# LM399.net
KiCad netlist of a schematic drawn in Altium Designer
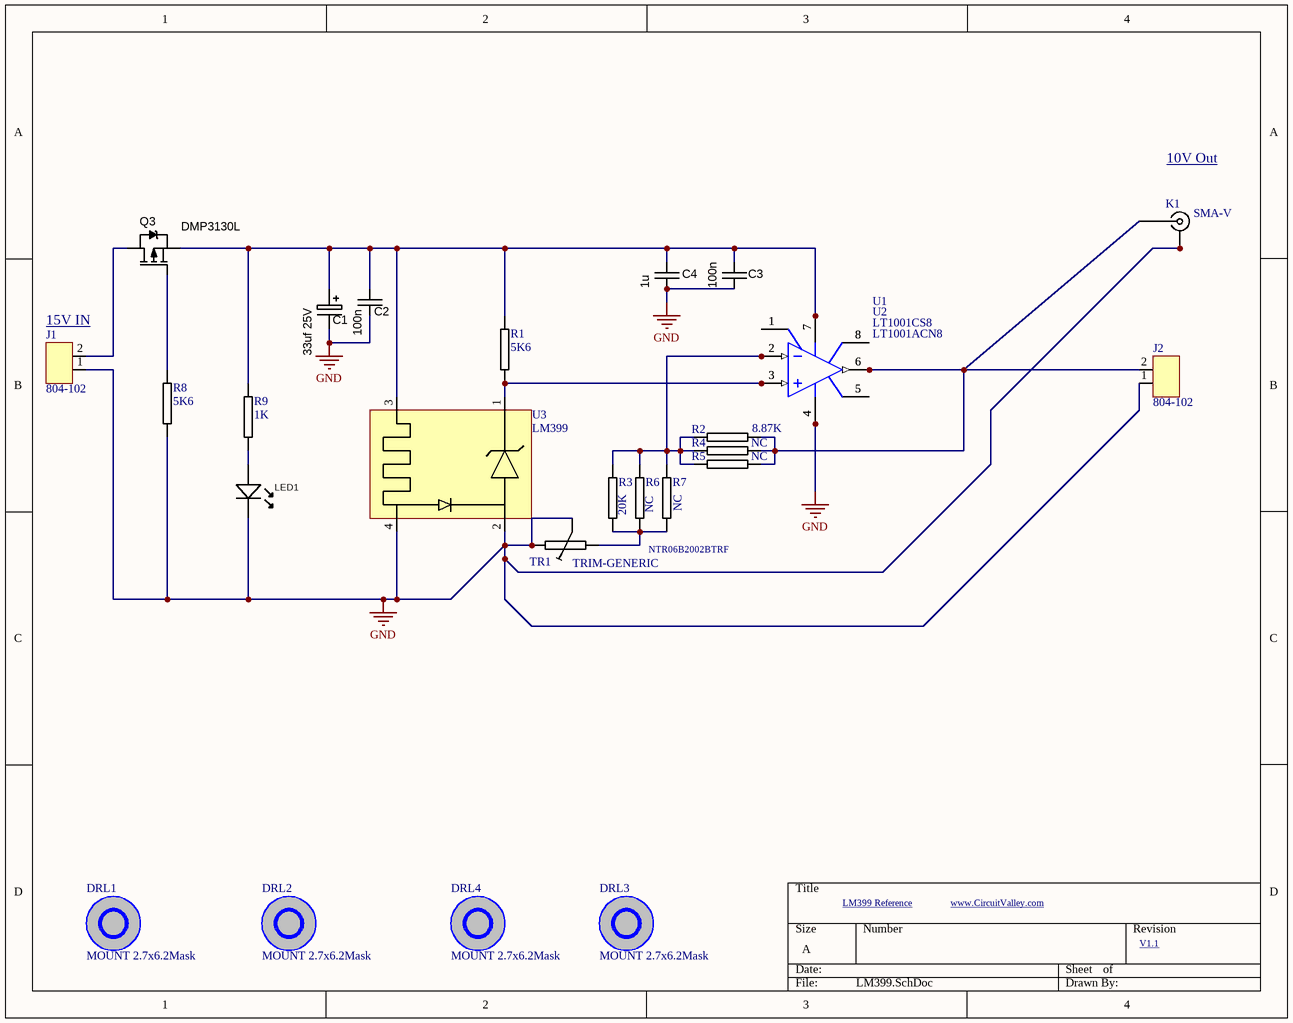
[diagram p0: LM399.SchDoc]

(export (version "E")
  (design (tool "Eeschema 10.0.6"))
  (components
    (comp (ref "C1")
      (value "33uf 25V")
      (footprint "CAPMP7343X310N")
      (description "Capacitor SMD Tant 330uF 20% 6V3 2917")
      (fields
        (field (name "TOLERANCE") "±20%")
        (field (name "MANUFACTURER PART NUMBER") "T520D337M006ATE015")
      )
      (libsource (lib "PBL - Capacitors") (part "CAPT_330u_2917_6V3"))
    )
    (comp (ref "C2")
      (value "100n")
      (footprint "CAPC1608N")
      (description "Capacitor SMD Cer 10pF 5% 50V NP0 0603")
      (fields (field (name "TOLERANCE") "±5%") (field (name "PART") "C0603X104K5RAC"))
      (libsource (lib "PBL - Capacitors") (part "CAPC_10p_0603_NP0_1%_50V"))
    )
    (comp (ref "C3")
      (value "100n")
      (footprint "CAPC1608N")
      (description "Capacitor SMD Cer 10pF 5% 50V NP0 0603")
      (fields (field (name "PART") "C0603X104K5RAC"))
      (libsource (lib "PBL - Capacitors") (part "CAPC_10p_0603_NP0_1%_50V"))
    )
    (comp (ref "C4")
      (value "1u")
      (footprint "CAPC1608N")
      (description "Capacitor SMD Cer 10pF 5% 50V NP0 0603")
      (fields (field (name "TOLERANCE") "±5%") (field (name "PART") "C0603X104K5RAC"))
      (libsource (lib "PBL - Capacitors") (part "CAPC_10p_0603_NP0_1%_50V"))
    )
    (comp (ref "DRL1")
      (value "MOUNT 2.7x6.2Mask")
      (footprint "NO_COPPER_NOMASK_2m75_6m2")
      (libsource (lib "mounting_hole") (part "DRILL_2.7x6.2Mask_NOCOPPER"))
    )
    (comp (ref "DRL2")
      (value "MOUNT 2.7x6.2Mask")
      (footprint "NO_COPPER_NOMASK_2m75_6m2")
      (libsource (lib "mounting_hole") (part "DRILL_2.7x6.2Mask_NOCOPPER"))
    )
    (comp (ref "DRL3")
      (value "MOUNT 2.7x6.2Mask")
      (footprint "NO_COPPER_NOMASK_2m75_6m2")
      (libsource (lib "mounting_hole") (part "DRILL_2.7x6.2Mask_NOCOPPER"))
    )
    (comp (ref "DRL4")
      (value "MOUNT 2.7x6.2Mask")
      (footprint "NO_COPPER_NOMASK_2m75_6m2")
      (libsource (lib "mounting_hole") (part "DRILL_2.7x6.2Mask_NOCOPPER"))
    )
    (comp (ref "J1") (value "804-102") (footprint "804-102") (libsource (lib "") (part "804-102_1")))
    (comp (ref "J2") (value "804-102") (footprint "804-102") (libsource (lib "cvlib") (part "804-102")))
    (comp (ref "K1")
      (value "SMA-V")
      (footprint "SMA-V")
      (description "SMA THREADED RF CONNECTOR VERTICAL")
      (libsource (lib "Generic") (part "SMA-V"))
    )
    (comp (ref "LED1")
      (value "~")
      (footprint "LED-0805-K")
      (description "LED, 0805 SMD, Green")
      (libsource (lib "PBL - Light Sources") (part "LED_SMD_Green_0805"))
    )
    (comp (ref "Q3")
      (value "DMP3130L")
      (footprint "SOT23-3")
      (description "MOSFET SMD P-CH 50V 130mA SOT23-3")
      (libsource (lib "PBL - Transistors") (part "MOSFET_BSS84"))
    )
    (comp (ref "R1")
      (value "5K6")
      (footprint "0603R-GENERIC")
      (description "GENERIC RESISTOR 0603")
      (fields (field (name "PART") "RMCF0603JT7K50"))
      (libsource (lib "Generic") (part "0603R-7K5"))
    )
    (comp (ref "R2")
      (value "8.87K")
      (footprint "0603R-TBD")
      (description "RESISTOR 0603 VALUE TO BE DETERMINED")
      (fields (field (name "PART") "RN73C1J8K87BTG"))
      (libsource (lib "Generic") (part "0603R-TBD"))
    )
    (comp (ref "R3")
      (value "20K")
      (footprint "0603R-GENERIC")
      (description "GENERIC RESISTOR 0603")
      (fields (field (name "PART") "ERA-3ARW203V"))
      (libsource (lib "Generic") (part "0603R-20K"))
    )
    (comp (ref "R4")
      (value "NC")
      (footprint "0603R-TBD")
      (description "RESISTOR 0603 VALUE TO BE DETERMINED")
      (fields (field (name "PART") "RN73C1J8K87BTG"))
      (libsource (lib "Generic") (part "0603R-TBD"))
    )
    (comp (ref "R5")
      (value "NC")
      (footprint "0603R-TBD")
      (description "RESISTOR 0603 VALUE TO BE DETERMINED")
      (fields (field (name "PART") "RN73C1J8K87BTG"))
      (libsource (lib "Generic") (part "0603R-TBD"))
    )
    (comp (ref "R6")
      (value "NC")
      (footprint "0603R-GENERIC")
      (description "GENERIC RESISTOR 0603")
      (fields (field (name "PART") "ERA-3ARW203V"))
      (libsource (lib "Generic") (part "0603R-20K"))
    )
    (comp (ref "R7")
      (value "NC")
      (footprint "0603R-GENERIC")
      (description "GENERIC RESISTOR 0603")
      (fields (field (name "PART") "ERA-3ARW203V"))
      (libsource (lib "Generic") (part "0603R-20K"))
    )
    (comp (ref "R8")
      (value "5K6")
      (footprint "0603R-GENERIC")
      (description "GENERIC RESISTOR 0603")
      (fields (field (name "PART") "RMCF0603JT7K50"))
      (libsource (lib "Generic") (part "0603R-7K5"))
    )
    (comp (ref "R9")
      (value "1K")
      (footprint "0603R-120K")
      (description "GENERIC RESISTOR 0603")
      (fields
        (field (name "MANUFACTURER") "Stackpole Electronics Inc")
        (field (name "MANUFACTURER PART NUMBER") "RMCF 1/16 120K 1% R")
      )
      (libsource (lib "Generic") (part "0603R-120K"))
    )
    (comp (ref "TR1")
      (value "TRIM-GENERIC")
      (footprint "TRIMMER-MT")
      (description "TRIMMABLE RESISTOR")
      (libsource (lib "Generic") (part "THTRIM-GENERIC"))
    )
    (comp (ref "U1")
      (value "LT1001CS8")
      (footprint "S8_N")
      (description "General Purpose, High Precision Op Amp")
      (fields (field (name "PART") "LT100ACN8"))
      (libsource (lib "LT Operational Amplifier") (part "LT1001CS8"))
    )
    (comp (ref "U2")
      (value "LT1001ACN8")
      (footprint "N8")
      (description "General Purpose, High Precision Op Amp")
      (fields (field (name "PUBLISHER") "Altium Limited"))
      (libsource (lib "LT Operational Amplifier") (part "LT1001ACN8"))
    )
    (comp (ref "U3") (value "LM399") (footprint "TO-46") (libsource (lib "cvlib") (part "LM399")))
  )
  (nets
    (net (code "1") (name "GND") (class "Default")
      (node (ref "C1") (pin "2") (pintype "passive"))
      (node (ref "C2") (pin "1") (pintype "passive"))
      (node (ref "C3") (pin "1") (pintype "passive"))
      (node (ref "C4") (pin "1") (pintype "passive"))
      (node (ref "J1") (pin "1") (pinfunction "PW_1") (pintype "passive"))
      (node (ref "J2") (pin "1") (pinfunction "PW_1") (pintype "passive"))
      (node (ref "K1") (pin "2") (pinfunction "2_2") (pintype "passive"))
      (node (ref "K1") (pin "3") (pinfunction "3_3") (pintype "passive"))
      (node (ref "K1") (pin "4") (pinfunction "4_4") (pintype "passive"))
      (node (ref "K1") (pin "5") (pinfunction "5_5") (pintype "passive"))
      (node (ref "LED1") (pin "K") (pinfunction "K_K") (pintype "passive"))
      (node (ref "R8") (pin "2") (pintype "passive"))
      (node (ref "TR1") (pin "2") (pinfunction "2_2") (pintype "passive"))
      (node (ref "TR1") (pin "W") (pinfunction "W_W") (pintype "passive"))
      (node (ref "U1") (pin "4") (pinfunction "V-_4") (pintype "power_in"))
      (node (ref "U2") (pin "4") (pinfunction "V-_4") (pintype "power_in"))
      (node (ref "U3") (pin "2") (pinfunction "D2_2") (pintype "passive"))
      (node (ref "U3") (pin "4") (pinfunction "H2_4") (pintype "passive"))
    )
    (net (code "2") (name "Net-(LED1-PadA)") (class "Default")
      (node (ref "LED1") (pin "A") (pinfunction "A_A") (pintype "passive"))
      (node (ref "R9") (pin "2") (pintype "passive"))
    )
    (net (code "3") (name "Net-(Q3-D)") (class "Default")
      (node (ref "J1") (pin "2") (pinfunction "PW_2") (pintype "passive"))
      (node (ref "Q3") (pin "3") (pinfunction "D_3") (pintype "passive"))
    )
    (net (code "4") (name "Net-(Q3-G)") (class "Default")
      (node (ref "Q3") (pin "1") (pinfunction "G_1") (pintype "passive"))
      (node (ref "R8") (pin "1") (pintype "passive"))
    )
    (net (code "5") (name "Net-(Q3-S)") (class "Default")
      (node (ref "C1") (pin "1") (pintype "passive"))
      (node (ref "C2") (pin "2") (pintype "passive"))
      (node (ref "C3") (pin "2") (pintype "passive"))
      (node (ref "C4") (pin "2") (pintype "passive"))
      (node (ref "Q3") (pin "2") (pinfunction "S_2") (pintype "passive"))
      (node (ref "R1") (pin "1") (pintype "passive"))
      (node (ref "R9") (pin "1") (pintype "passive"))
      (node (ref "U1") (pin "7") (pinfunction "V+_7") (pintype "power_in"))
      (node (ref "U2") (pin "7") (pinfunction "V+_7") (pintype "power_in"))
      (node (ref "U3") (pin "3") (pinfunction "H1_3") (pintype "passive"))
    )
    (net (code "6") (name "Net-(R3-Pad1)") (class "Default")
      (node (ref "R3") (pin "1") (pintype "passive"))
      (node (ref "R6") (pin "1") (pintype "passive"))
      (node (ref "R7") (pin "1") (pintype "passive"))
      (node (ref "TR1") (pin "1") (pinfunction "1_1") (pintype "passive"))
    )
    (net (code "7") (name "Net-(U1-IN+)") (class "Default")
      (node (ref "R1") (pin "2") (pintype "passive"))
      (node (ref "U1") (pin "3") (pinfunction "IN+_3") (pintype "input"))
      (node (ref "U2") (pin "3") (pinfunction "IN+_3") (pintype "input"))
      (node (ref "U3") (pin "1") (pinfunction "D1_1") (pintype "passive"))
    )
    (net (code "8") (name "Net-(U1-IN-)") (class "Default")
      (node (ref "R2") (pin "1") (pintype "passive"))
      (node (ref "R3") (pin "2") (pintype "passive"))
      (node (ref "R4") (pin "1") (pintype "passive"))
      (node (ref "R5") (pin "1") (pintype "passive"))
      (node (ref "R6") (pin "2") (pintype "passive"))
      (node (ref "R7") (pin "2") (pintype "passive"))
      (node (ref "U1") (pin "2") (pinfunction "IN-_2") (pintype "input"))
      (node (ref "U2") (pin "2") (pinfunction "IN-_2") (pintype "input"))
    )
    (net (code "9") (name "Net-(U1-NC)") (class "Default")
      (node (ref "U1") (pin "5") (pinfunction "NC_5") (pintype "passive"))
      (node (ref "U2") (pin "5") (pinfunction "NC_5") (pintype "passive"))
    )
    (net (code "10") (name "Net-(U1-OUT)") (class "Default")
      (node (ref "J2") (pin "2") (pinfunction "PW_2") (pintype "passive"))
      (node (ref "K1") (pin "1") (pinfunction "1_1") (pintype "passive"))
      (node (ref "R2") (pin "2") (pintype "passive"))
      (node (ref "R4") (pin "2") (pintype "passive"))
      (node (ref "R5") (pin "2") (pintype "passive"))
      (node (ref "U1") (pin "6") (pinfunction "OUT_6") (pintype "output"))
      (node (ref "U2") (pin "6") (pinfunction "OUT_6") (pintype "output"))
    )
    (net (code "11") (name "Net-(U1-VOSTRIM-Pad1)") (class "Default")
      (node (ref "U1") (pin "1") (pinfunction "VOSTRIM_1") (pintype "passive"))
      (node (ref "U2") (pin "1") (pinfunction "VOSTRIM_1") (pintype "passive"))
    )
    (net (code "12") (name "Net-(U1-VOSTRIM-Pad8)") (class "Default")
      (node (ref "U1") (pin "8") (pinfunction "VOSTRIM_8") (pintype "passive"))
      (node (ref "U2") (pin "8") (pinfunction "VOSTRIM_8") (pintype "passive"))
    )
  )
)
